# pi-crust.net
KiCad netlist of a schematic drawn in EAGLE
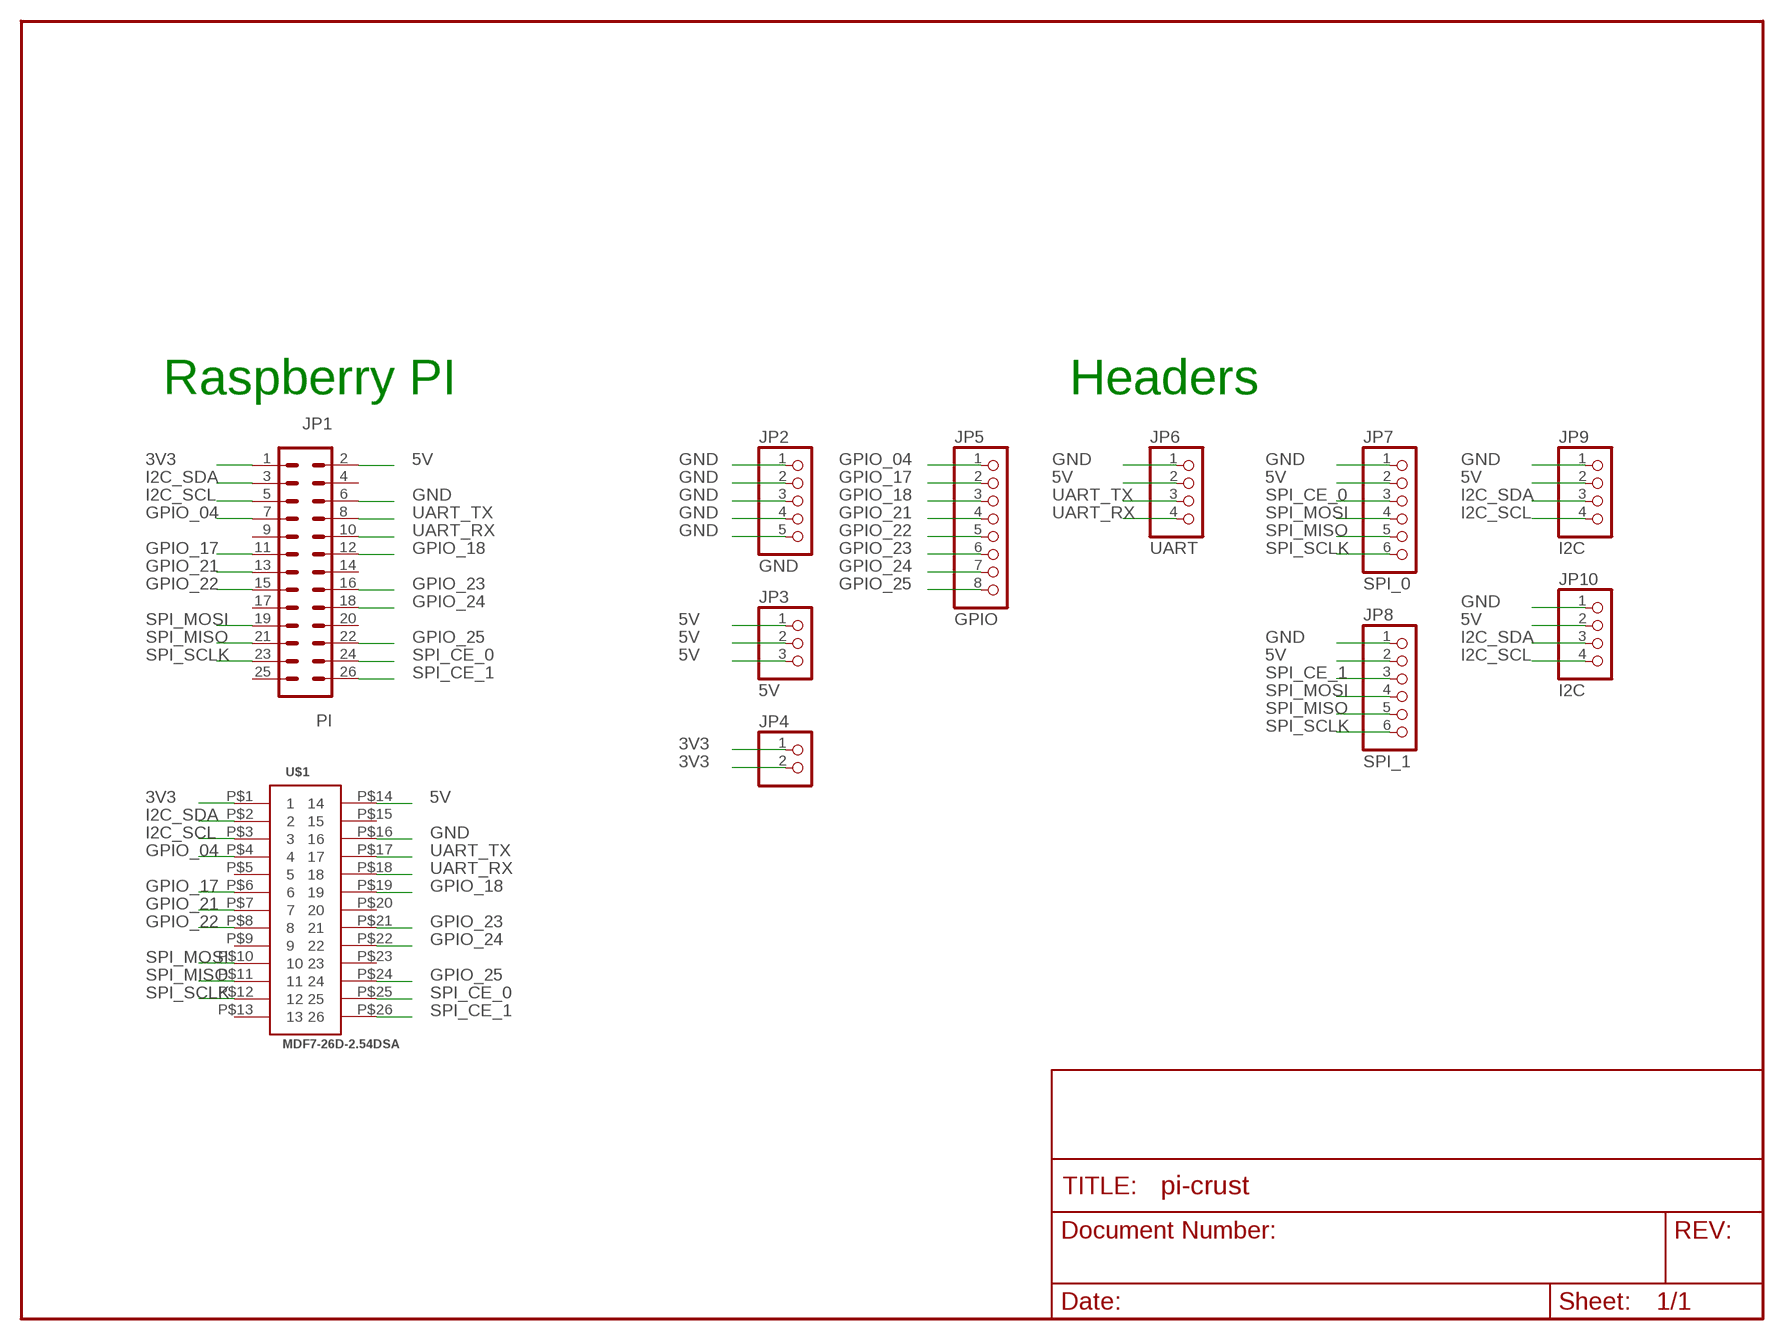
[diagram p0: schematic, sheet 1]

(export (version "E")
  (design (tool "Eeschema 10.0.6"))
  (components
    (comp (ref "JP1")
      (value "PI")
      (footprint "eagle-import:MA13-2")
      (libsource (lib "eagle-import") (part "MA13-2"))
    )
    (comp (ref "JP2")
      (value "GND")
      (footprint "eagle-import:1X05")
      (libsource (lib "eagle-import") (part "PINHD-1X5"))
    )
    (comp (ref "JP3")
      (value "5V")
      (footprint "eagle-import:1X03")
      (libsource (lib "eagle-import") (part "PINHD-1X3"))
    )
    (comp (ref "JP4")
      (value "PINHD-1X2")
      (footprint "eagle-import:1X02")
      (libsource (lib "eagle-import") (part "PINHD-1X2"))
    )
    (comp (ref "JP5")
      (value "GPIO")
      (footprint "eagle-import:1X08")
      (libsource (lib "eagle-import") (part "PINHD-1X8"))
    )
    (comp (ref "JP6")
      (value "UART")
      (footprint "eagle-import:1X04")
      (libsource (lib "eagle-import") (part "PINHD-1X4"))
    )
    (comp (ref "JP7")
      (value "SPI_0")
      (footprint "eagle-import:1X06")
      (libsource (lib "eagle-import") (part "PINHD-1X6"))
    )
    (comp (ref "JP8")
      (value "SPI_1")
      (footprint "eagle-import:1X06")
      (libsource (lib "eagle-import") (part "PINHD-1X6"))
    )
    (comp (ref "JP9")
      (value "I2C")
      (footprint "eagle-import:1X04")
      (libsource (lib "eagle-import") (part "PINHD-1X4"))
    )
    (comp (ref "JP10")
      (value "I2C")
      (footprint "eagle-import:1X04")
      (libsource (lib "eagle-import") (part "PINHD-1X4"))
    )
    (comp (ref "U$1")
      (value "MDF7-26D-2.54DSA")
      (footprint "eagle-import:MDF7-26D-2.54DSA")
      (libsource (lib "eagle-import") (part "MDF7-26D-2.54DSA"))
    )
  )
  (nets
    (net (code "1") (name "/3V3") (class "Default")
      (node (ref "JP1") (pin "1") (pinfunction "1_1") (pintype "passive"))
      (node (ref "JP4") (pin "1") (pinfunction "1_1") (pintype "passive"))
      (node (ref "JP4") (pin "2") (pinfunction "2_2") (pintype "passive"))
      (node (ref "U$1") (pin "P$1") (pinfunction "1_P$1") (pintype "bidirectional"))
    )
    (net (code "2") (name "/5V") (class "Default")
      (node (ref "JP1") (pin "2") (pinfunction "2_2") (pintype "passive"))
      (node (ref "JP10") (pin "2") (pinfunction "2_2") (pintype "passive"))
      (node (ref "JP3") (pin "1") (pinfunction "1_1") (pintype "passive"))
      (node (ref "JP3") (pin "2") (pinfunction "2_2") (pintype "passive"))
      (node (ref "JP3") (pin "3") (pinfunction "3_3") (pintype "passive"))
      (node (ref "JP6") (pin "2") (pinfunction "2_2") (pintype "passive"))
      (node (ref "JP7") (pin "2") (pinfunction "2_2") (pintype "passive"))
      (node (ref "JP8") (pin "2") (pinfunction "2_2") (pintype "passive"))
      (node (ref "JP9") (pin "2") (pinfunction "2_2") (pintype "passive"))
      (node (ref "U$1") (pin "P$14") (pinfunction "14_P$14") (pintype "bidirectional"))
    )
    (net (code "3") (name "/GND") (class "Default")
      (node (ref "JP1") (pin "6") (pinfunction "6_6") (pintype "passive"))
      (node (ref "JP10") (pin "1") (pinfunction "1_1") (pintype "passive"))
      (node (ref "JP2") (pin "1") (pinfunction "1_1") (pintype "passive"))
      (node (ref "JP2") (pin "2") (pinfunction "2_2") (pintype "passive"))
      (node (ref "JP2") (pin "3") (pinfunction "3_3") (pintype "passive"))
      (node (ref "JP2") (pin "4") (pinfunction "4_4") (pintype "passive"))
      (node (ref "JP2") (pin "5") (pinfunction "5_5") (pintype "passive"))
      (node (ref "JP6") (pin "1") (pinfunction "1_1") (pintype "passive"))
      (node (ref "JP7") (pin "1") (pinfunction "1_1") (pintype "passive"))
      (node (ref "JP8") (pin "1") (pinfunction "1_1") (pintype "passive"))
      (node (ref "JP9") (pin "1") (pinfunction "1_1") (pintype "passive"))
      (node (ref "U$1") (pin "P$16") (pinfunction "16_P$16") (pintype "bidirectional"))
    )
    (net (code "4") (name "/GPIO_04") (class "Default")
      (node (ref "JP1") (pin "7") (pinfunction "7_7") (pintype "passive"))
      (node (ref "JP5") (pin "1") (pinfunction "1_1") (pintype "passive"))
      (node (ref "U$1") (pin "P$4") (pinfunction "4_P$4") (pintype "bidirectional"))
    )
    (net (code "5") (name "/GPIO_17") (class "Default")
      (node (ref "JP1") (pin "11") (pinfunction "11_11") (pintype "passive"))
      (node (ref "JP5") (pin "2") (pinfunction "2_2") (pintype "passive"))
      (node (ref "U$1") (pin "P$6") (pinfunction "6_P$6") (pintype "bidirectional"))
    )
    (net (code "6") (name "/GPIO_18") (class "Default")
      (node (ref "JP1") (pin "12") (pinfunction "12_12") (pintype "passive"))
      (node (ref "JP5") (pin "3") (pinfunction "3_3") (pintype "passive"))
      (node (ref "U$1") (pin "P$19") (pinfunction "19_P$19") (pintype "bidirectional"))
    )
    (net (code "7") (name "/GPIO_21") (class "Default")
      (node (ref "JP1") (pin "13") (pinfunction "13_13") (pintype "passive"))
      (node (ref "JP5") (pin "4") (pinfunction "4_4") (pintype "passive"))
      (node (ref "U$1") (pin "P$7") (pinfunction "7_P$7") (pintype "bidirectional"))
    )
    (net (code "8") (name "/GPIO_22") (class "Default")
      (node (ref "JP1") (pin "15") (pinfunction "15_15") (pintype "passive"))
      (node (ref "JP5") (pin "5") (pinfunction "5_5") (pintype "passive"))
      (node (ref "U$1") (pin "P$8") (pinfunction "8_P$8") (pintype "bidirectional"))
    )
    (net (code "9") (name "/GPIO_23") (class "Default")
      (node (ref "JP1") (pin "16") (pinfunction "16_16") (pintype "passive"))
      (node (ref "JP5") (pin "6") (pinfunction "6_6") (pintype "passive"))
      (node (ref "U$1") (pin "P$21") (pinfunction "21_P$21") (pintype "bidirectional"))
    )
    (net (code "10") (name "/GPIO_24") (class "Default")
      (node (ref "JP1") (pin "18") (pinfunction "18_18") (pintype "passive"))
      (node (ref "JP5") (pin "7") (pinfunction "7_7") (pintype "passive"))
      (node (ref "U$1") (pin "P$22") (pinfunction "22_P$22") (pintype "bidirectional"))
    )
    (net (code "11") (name "/GPIO_25") (class "Default")
      (node (ref "JP1") (pin "22") (pinfunction "22_22") (pintype "passive"))
      (node (ref "JP5") (pin "8") (pinfunction "8_8") (pintype "passive"))
      (node (ref "U$1") (pin "P$24") (pinfunction "24_P$24") (pintype "bidirectional"))
    )
    (net (code "12") (name "/I2C_SCL") (class "Default")
      (node (ref "JP1") (pin "5") (pinfunction "5_5") (pintype "passive"))
      (node (ref "JP10") (pin "4") (pinfunction "4_4") (pintype "passive"))
      (node (ref "JP9") (pin "4") (pinfunction "4_4") (pintype "passive"))
      (node (ref "U$1") (pin "P$3") (pinfunction "3_P$3") (pintype "bidirectional"))
    )
    (net (code "13") (name "/I2C_SDA") (class "Default")
      (node (ref "JP1") (pin "3") (pinfunction "3_3") (pintype "passive"))
      (node (ref "JP10") (pin "3") (pinfunction "3_3") (pintype "passive"))
      (node (ref "JP9") (pin "3") (pinfunction "3_3") (pintype "passive"))
      (node (ref "U$1") (pin "P$2") (pinfunction "2_P$2") (pintype "bidirectional"))
    )
    (net (code "14") (name "/SPI_CE_0") (class "Default")
      (node (ref "JP1") (pin "24") (pinfunction "24_24") (pintype "passive"))
      (node (ref "JP7") (pin "3") (pinfunction "3_3") (pintype "passive"))
      (node (ref "U$1") (pin "P$25") (pinfunction "25_P$25") (pintype "bidirectional"))
    )
    (net (code "15") (name "/SPI_CE_1") (class "Default")
      (node (ref "JP1") (pin "26") (pinfunction "26_26") (pintype "passive"))
      (node (ref "JP8") (pin "3") (pinfunction "3_3") (pintype "passive"))
      (node (ref "U$1") (pin "P$26") (pinfunction "26_P$26") (pintype "bidirectional"))
    )
    (net (code "16") (name "/SPI_MISO") (class "Default")
      (node (ref "JP1") (pin "21") (pinfunction "21_21") (pintype "passive"))
      (node (ref "JP7") (pin "5") (pinfunction "5_5") (pintype "passive"))
      (node (ref "JP8") (pin "5") (pinfunction "5_5") (pintype "passive"))
      (node (ref "U$1") (pin "P$11") (pinfunction "11_P$11") (pintype "bidirectional"))
    )
    (net (code "17") (name "/SPI_MOSI") (class "Default")
      (node (ref "JP1") (pin "19") (pinfunction "19_19") (pintype "passive"))
      (node (ref "JP7") (pin "4") (pinfunction "4_4") (pintype "passive"))
      (node (ref "JP8") (pin "4") (pinfunction "4_4") (pintype "passive"))
      (node (ref "U$1") (pin "P$10") (pinfunction "10_P$10") (pintype "bidirectional"))
    )
    (net (code "18") (name "/SPI_SCLK") (class "Default")
      (node (ref "JP1") (pin "23") (pinfunction "23_23") (pintype "passive"))
      (node (ref "JP7") (pin "6") (pinfunction "6_6") (pintype "passive"))
      (node (ref "JP8") (pin "6") (pinfunction "6_6") (pintype "passive"))
      (node (ref "U$1") (pin "P$12") (pinfunction "12_P$12") (pintype "bidirectional"))
    )
    (net (code "19") (name "/UART_RX") (class "Default")
      (node (ref "JP1") (pin "10") (pinfunction "10_10") (pintype "passive"))
      (node (ref "JP6") (pin "4") (pinfunction "4_4") (pintype "passive"))
      (node (ref "U$1") (pin "P$18") (pinfunction "18_P$18") (pintype "bidirectional"))
    )
    (net (code "20") (name "/UART_TX") (class "Default")
      (node (ref "JP1") (pin "8") (pinfunction "8_8") (pintype "passive"))
      (node (ref "JP6") (pin "3") (pinfunction "3_3") (pintype "passive"))
      (node (ref "U$1") (pin "P$17") (pinfunction "17_P$17") (pintype "bidirectional"))
    )
    (net (code "21") (name "unconnected-(JP1-Pad4)") (class "Default")
      (node (ref "JP1") (pin "4") (pinfunction "4_4") (pintype "passive"))
    )
    (net (code "22") (name "unconnected-(JP1-Pad9)") (class "Default")
      (node (ref "JP1") (pin "9") (pinfunction "9_9") (pintype "passive"))
    )
    (net (code "23") (name "unconnected-(JP1-Pad14)") (class "Default")
      (node (ref "JP1") (pin "14") (pinfunction "14_14") (pintype "passive"))
    )
    (net (code "24") (name "unconnected-(JP1-Pad17)") (class "Default")
      (node (ref "JP1") (pin "17") (pinfunction "17_17") (pintype "passive"))
    )
    (net (code "25") (name "unconnected-(JP1-Pad20)") (class "Default")
      (node (ref "JP1") (pin "20") (pinfunction "20_20") (pintype "passive"))
    )
    (net (code "26") (name "unconnected-(JP1-Pad25)") (class "Default")
      (node (ref "JP1") (pin "25") (pinfunction "25_25") (pintype "passive"))
    )
    (net (code "27") (name "unconnected-(U$1-5-PadP$5)") (class "Default")
      (node (ref "U$1") (pin "P$5") (pinfunction "5_P$5") (pintype "bidirectional"))
    )
    (net (code "28") (name "unconnected-(U$1-9-PadP$9)") (class "Default")
      (node (ref "U$1") (pin "P$9") (pinfunction "9_P$9") (pintype "bidirectional"))
    )
    (net (code "29") (name "unconnected-(U$1-13-PadP$13)") (class "Default")
      (node (ref "U$1") (pin "P$13") (pinfunction "13_P$13") (pintype "bidirectional"))
    )
    (net (code "30") (name "unconnected-(U$1-15-PadP$15)") (class "Default")
      (node (ref "U$1") (pin "P$15") (pinfunction "15_P$15") (pintype "bidirectional"))
    )
    (net (code "31") (name "unconnected-(U$1-20-PadP$20)") (class "Default")
      (node (ref "U$1") (pin "P$20") (pinfunction "20_P$20") (pintype "bidirectional"))
    )
    (net (code "32") (name "unconnected-(U$1-23-PadP$23)") (class "Default")
      (node (ref "U$1") (pin "P$23") (pinfunction "23_P$23") (pintype "bidirectional"))
    )
  )
)
